# 1-Schematic_Antenna_Mini-Whip_SMD.net
KiCad netlist of a schematic drawn in EasyEDA
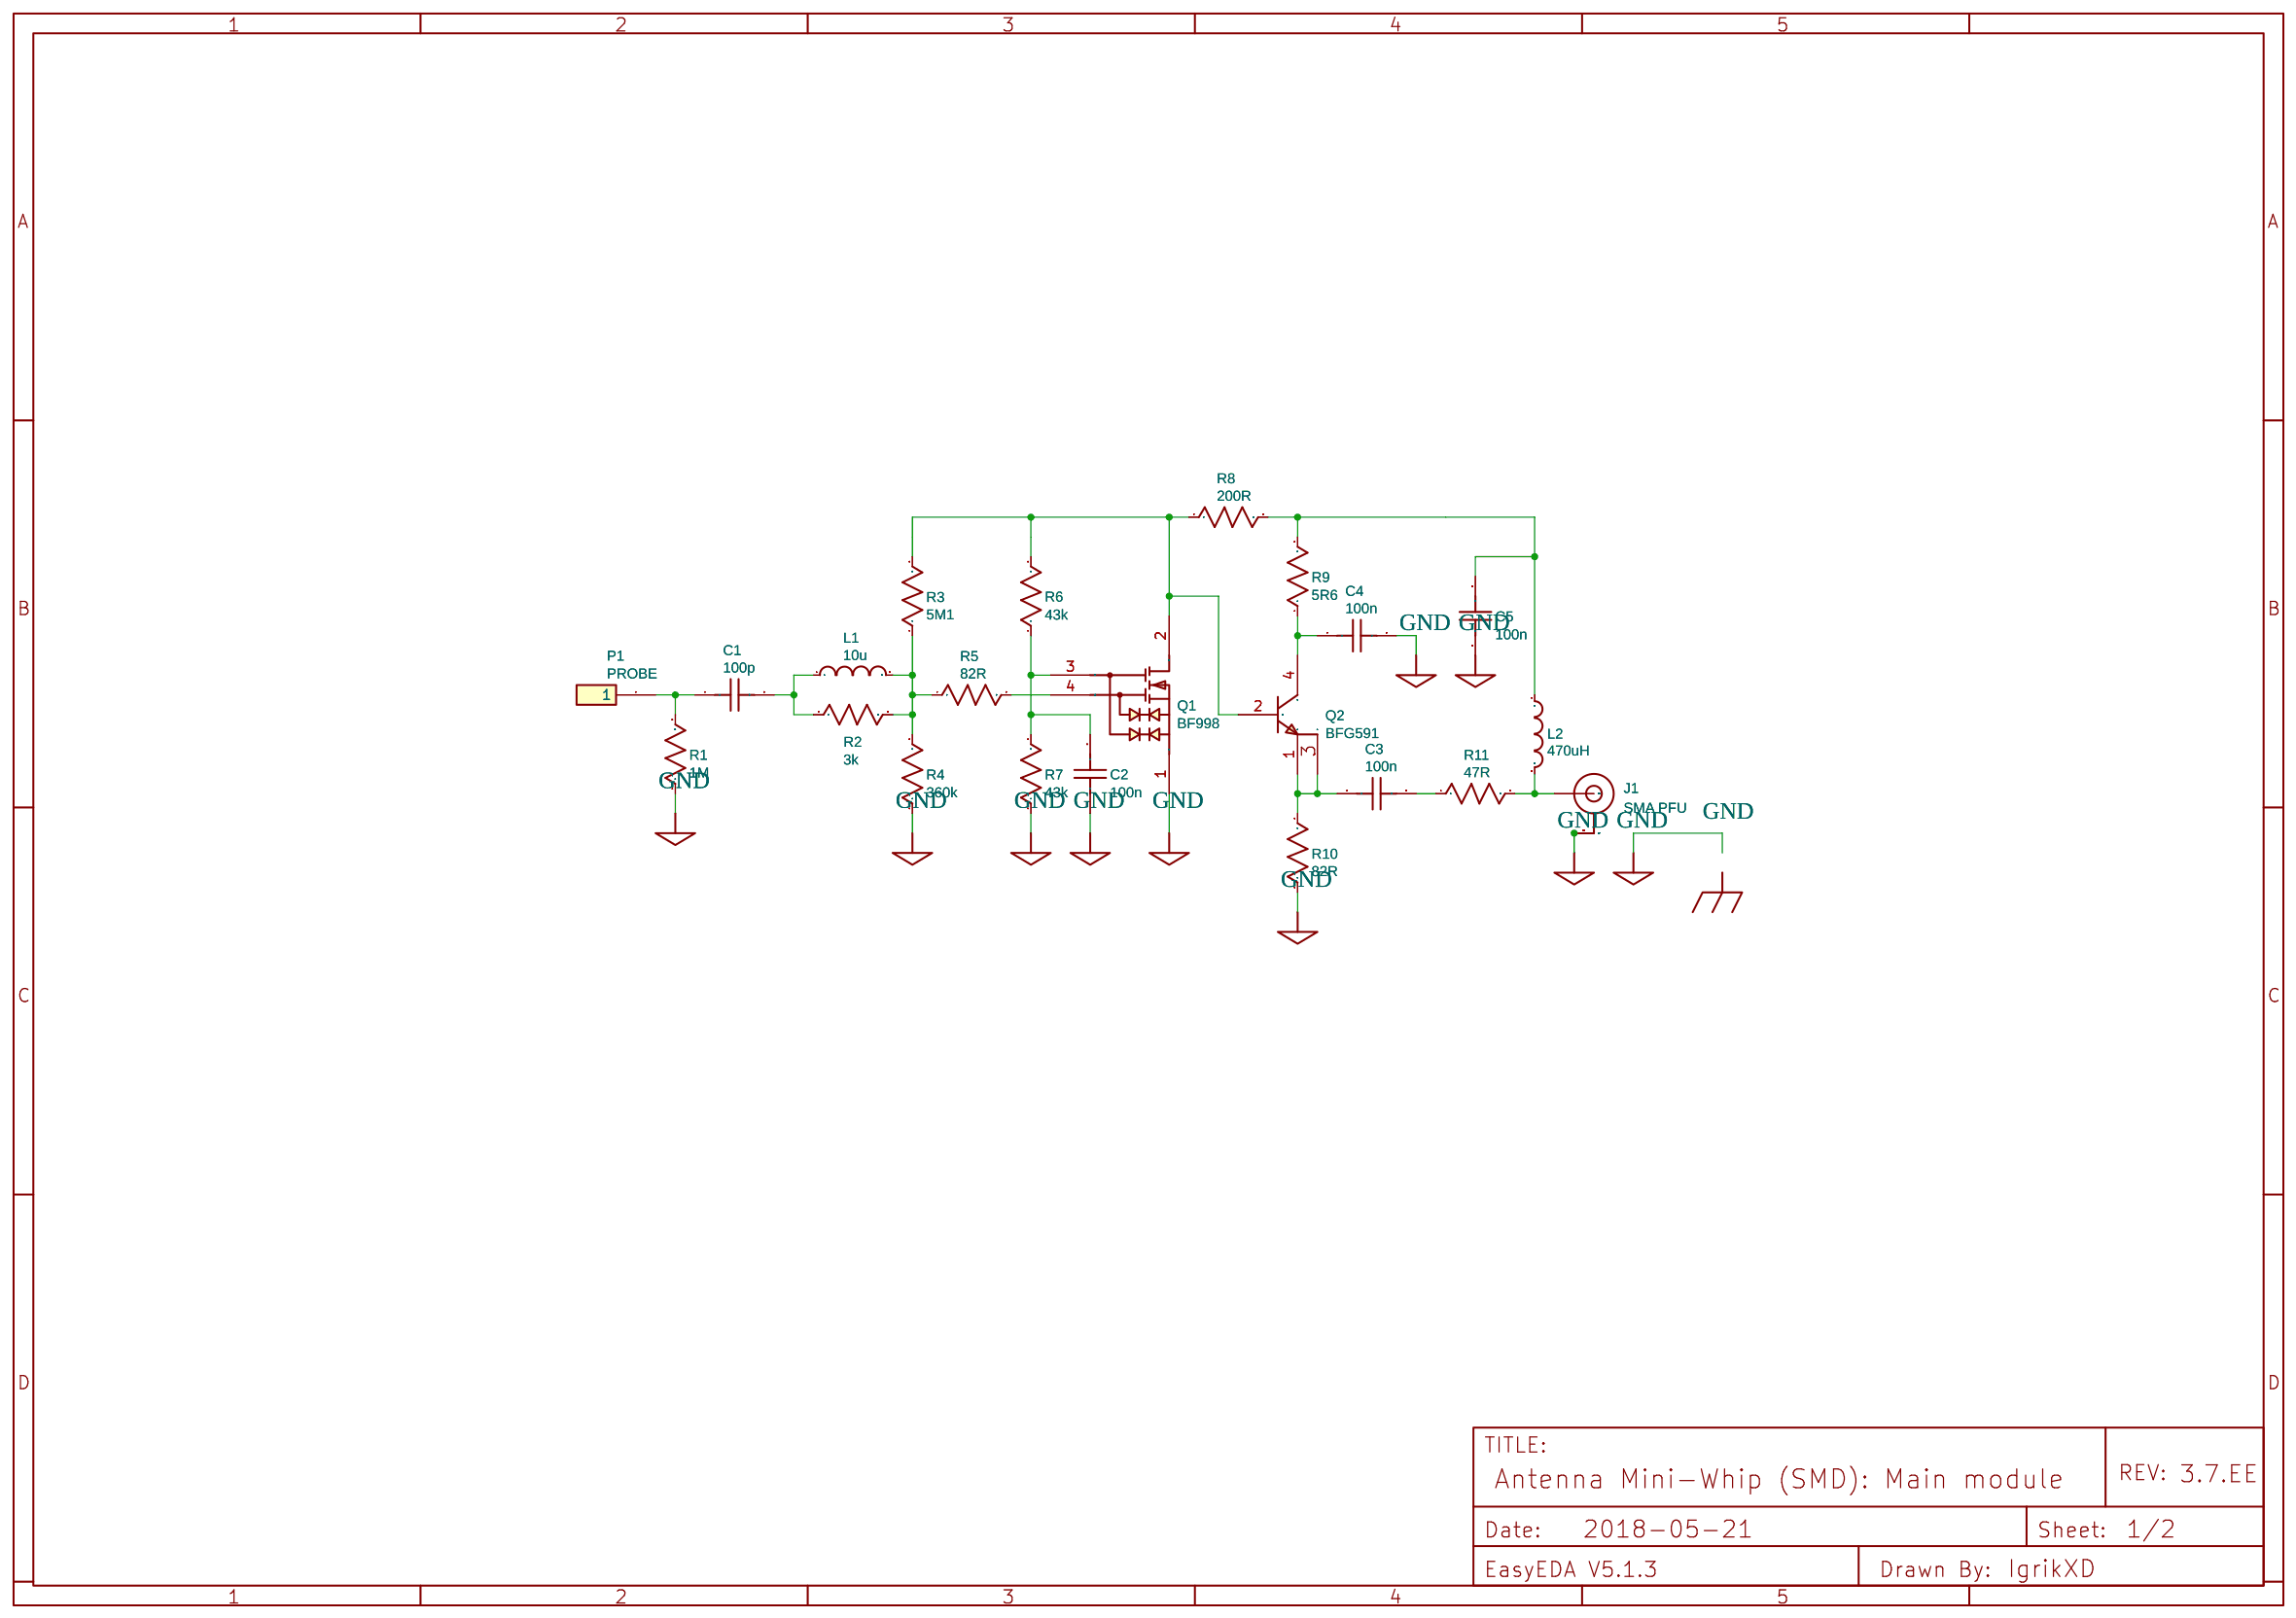
[diagram p0: Antenna Mini-Whip (SMD): Main module]
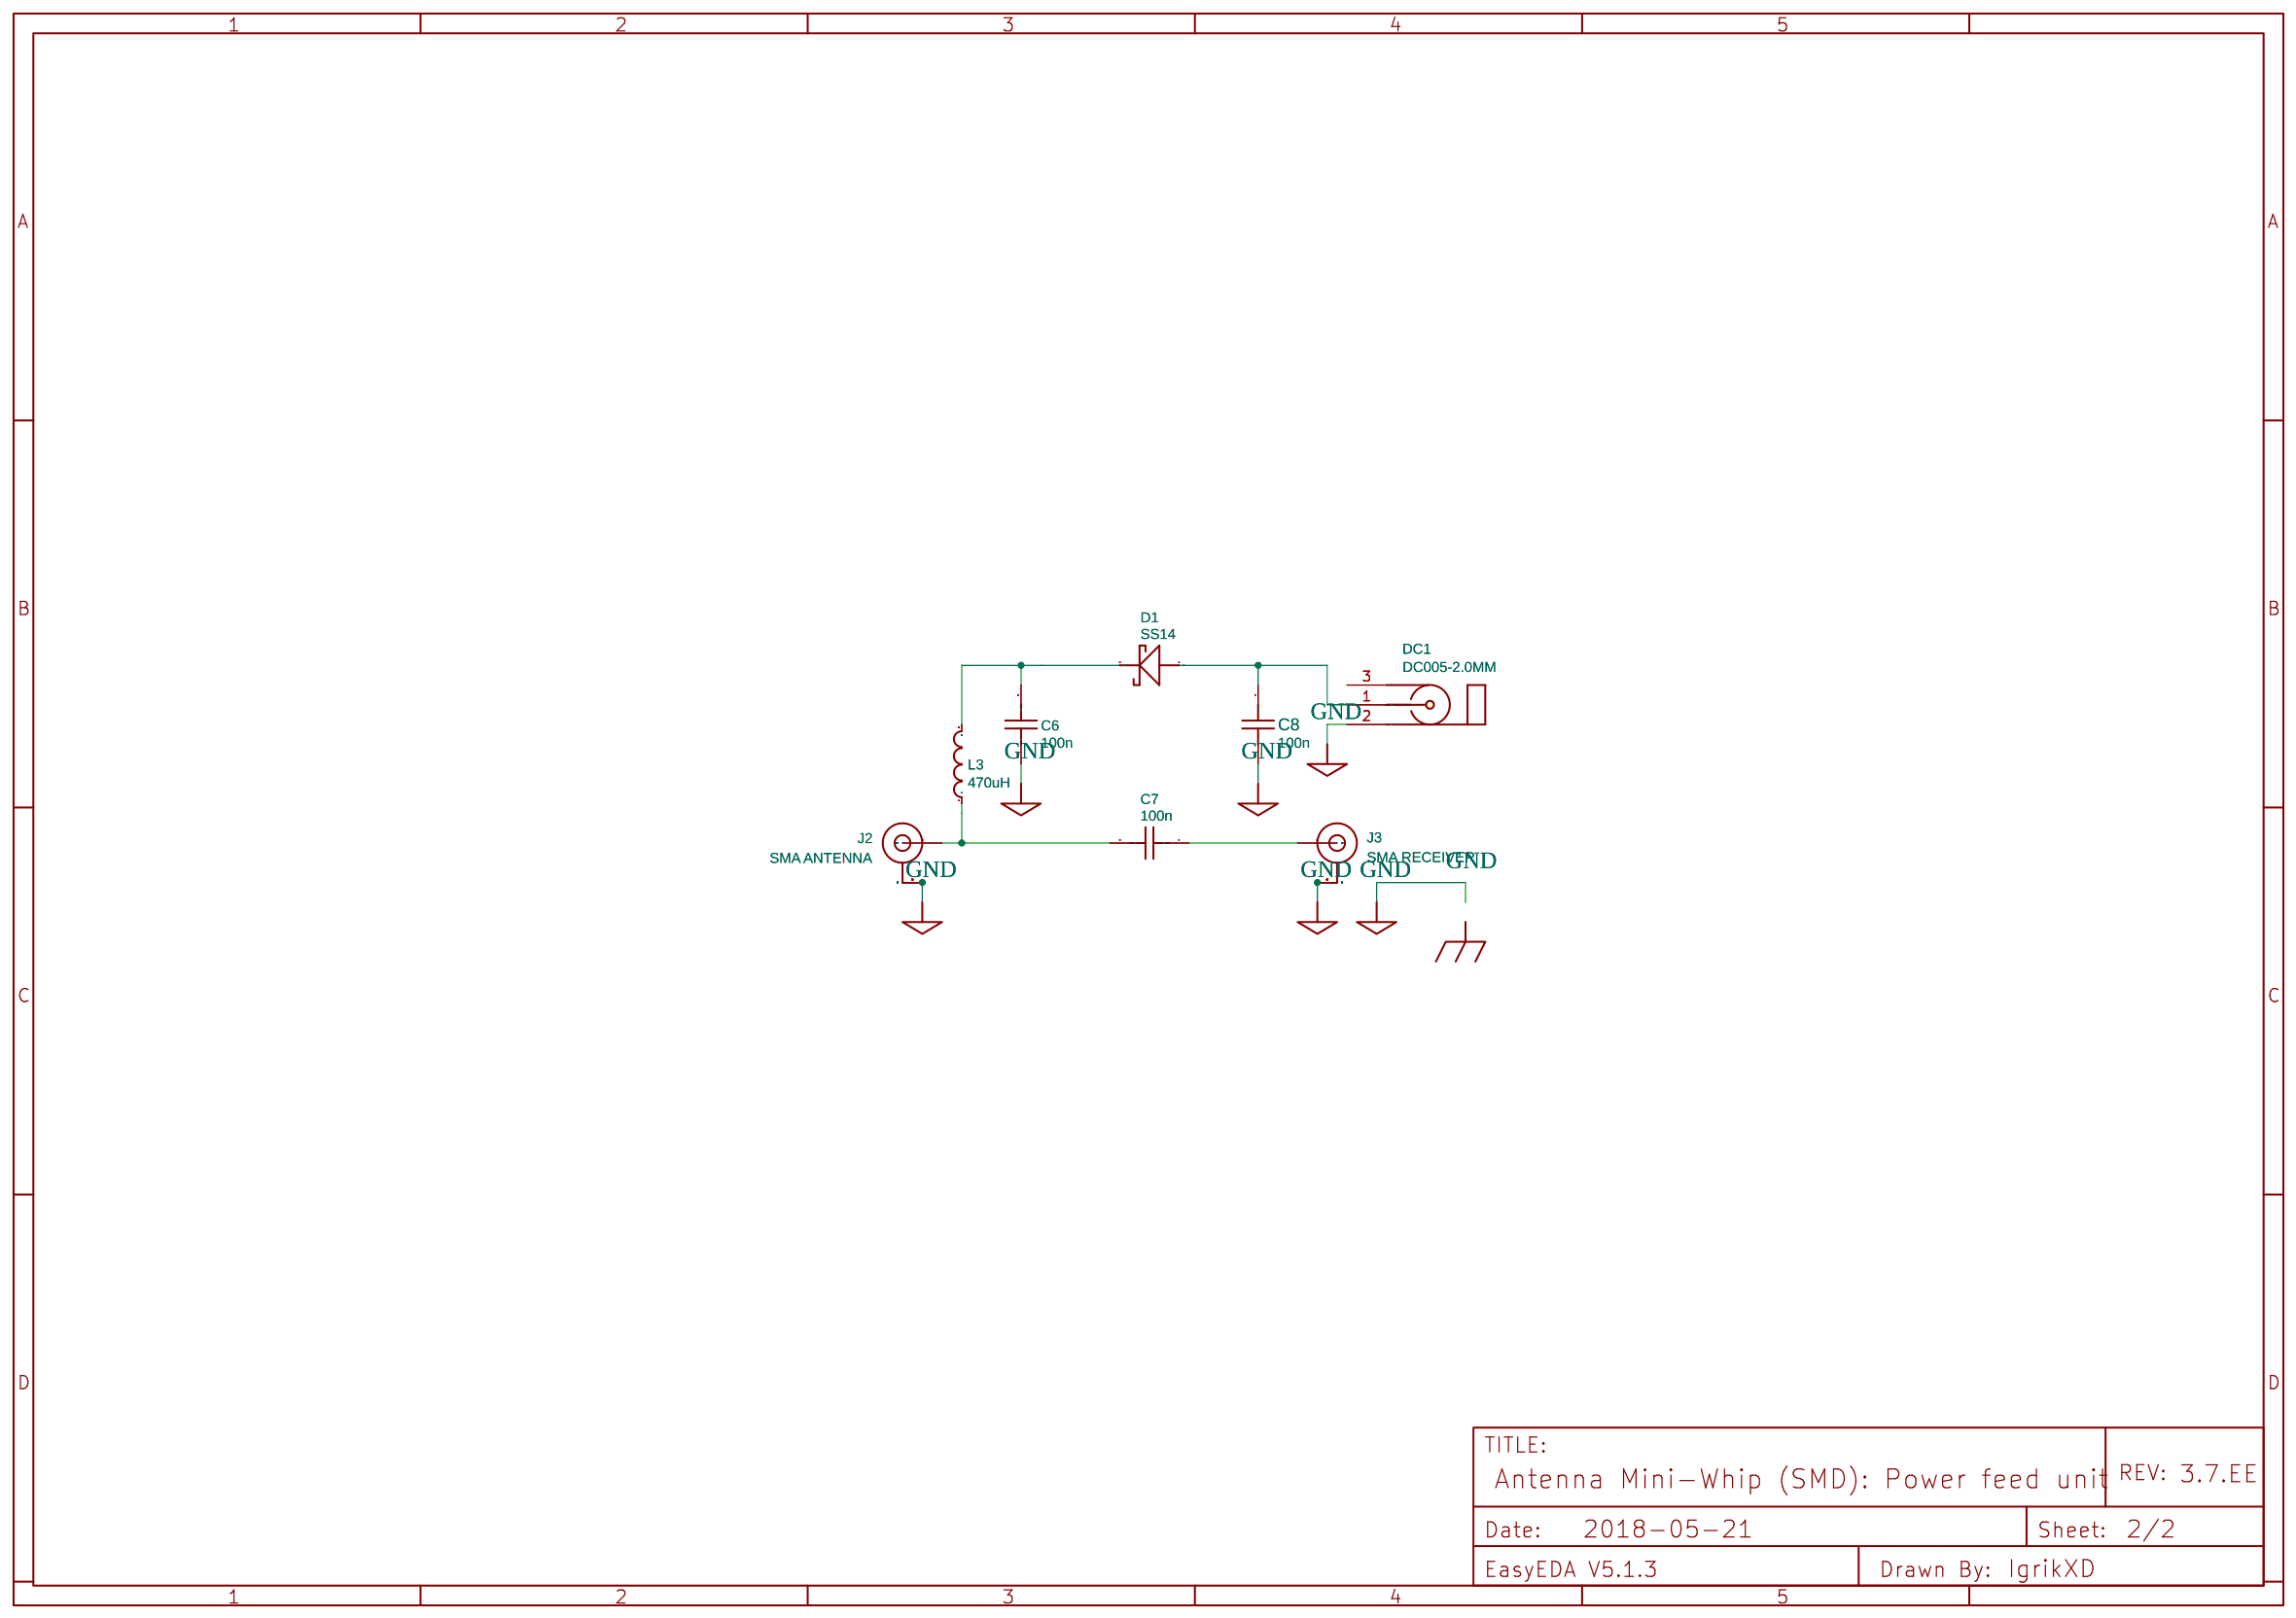
[diagram p1: Antenna Mini-Whip (SMD): Power feed unit]

(export (version "E")
  (design (tool "Eeschema 10.0.6"))
  (components
    (comp (ref "C1")
      (value "100p")
      (fields (field (name "BOM_Manufacturer Part") "CC0805JRNPOBBN101"))
      (libsource (lib "") (part "Capacitor"))
    )
    (comp (ref "C2")
      (value "100n")
      (fields (field (name "BOM_Manufacturer Part") "08055C104JAT2A"))
      (libsource (lib "") (part "Capacitor_1"))
    )
    (comp (ref "C3")
      (value "100n")
      (fields (field (name "BOM_Manufacturer Part") "08055C104JAT2A"))
      (libsource (lib "") (part "Capacitor"))
    )
    (comp (ref "C4")
      (value "100n")
      (fields (field (name "BOM_Manufacturer Part") "08055C104JAT2A"))
      (libsource (lib "") (part "Capacitor"))
    )
    (comp (ref "C5")
      (value "100n")
      (fields (field (name "BOM_Manufacturer Part") "08055C104JAT2A"))
      (libsource (lib "") (part "Capacitor_1"))
    )
    (comp (ref "J1")
      (value "SMA PFU")
      (fields (field (name "BOM_Manufacturer Part") "ANKX01.0093"))
      (libsource (lib "") (part "Unknown_800_395"))
    )
    (comp (ref "L1")
      (value "10u")
      (fields (field (name "BOM_Manufacturer Part") "MLF2012E100JT000"))
      (libsource (lib "") (part "Inductor"))
    )
    (comp (ref "L2")
      (value "470uH")
      (fields (field (name "BOM_Manufacturer Part") "SM7850-471MT"))
      (libsource (lib "") (part "Unknown_770_365"))
    )
    (comp (ref "P1")
      (value "PROBE")
      (fields (field (name "BOM_Manufacturer Part") "Header-Male-2.54_1x1"))
      (libsource (lib "") (part "Unknown_310_345"))
    )
    (comp (ref "Q1")
      (value "BF998")
      (fields (field (name "BOM_Manufacturer Part") "BF998E6327HTSA1"))
      (libsource (lib "") (part "Unknown_565_355"))
    )
    (comp (ref "Q2")
      (value "BFG591")
      (fields (field (name "BOM_Manufacturer Part") "BFG591,115"))
      (libsource (lib "") (part "Unknown_640_355"))
    )
    (comp (ref "R1")
      (value "1M")
      (fields (field (name "BOM_Manufacturer Part") "RC0805FR-071ML"))
      (libsource (lib "") (part "Resistor_1"))
    )
    (comp (ref "R2")
      (value "3k")
      (fields (field (name "BOM_Manufacturer Part") "RC0805FR-073KL"))
      (libsource (lib "") (part "Resistor"))
    )
    (comp (ref "R3")
      (value "5M1")
      (fields (field (name "BOM_Manufacturer Part") "RC0805FR-075M1L"))
      (libsource (lib "") (part "Resistor_1"))
    )
    (comp (ref "R4")
      (value "360k")
      (fields (field (name "BOM_Manufacturer Part") "RC0805FR-07360KL"))
      (libsource (lib "") (part "Resistor_1"))
    )
    (comp (ref "R5")
      (value "82R")
      (fields (field (name "BOM_Manufacturer Part") "RTT0582R0FTP"))
      (libsource (lib "") (part "Resistor"))
    )
    (comp (ref "R6")
      (value "43k")
      (fields (field (name "BOM_Manufacturer Part") "RTT054302FTP"))
      (libsource (lib "") (part "Resistor_1"))
    )
    (comp (ref "R7")
      (value "43k")
      (fields (field (name "BOM_Manufacturer Part") "RTT054302FTP"))
      (libsource (lib "") (part "Resistor_1"))
    )
    (comp (ref "R8")
      (value "200R")
      (fields (field (name "BOM_Manufacturer Part") "RC1206FR-07200RL"))
      (libsource (lib "") (part "Resistor"))
    )
    (comp (ref "R9")
      (value "5R6")
      (fields (field (name "BOM_Manufacturer Part") "CR0805F85R60G"))
      (libsource (lib "") (part "Resistor_1"))
    )
    (comp (ref "R10")
      (value "82R")
      (fields (field (name "BOM_Manufacturer Part") "CR2512J82RE042W"))
      (libsource (lib "") (part "Resistor_1"))
    )
    (comp (ref "R11")
      (value "47R")
      (fields (field (name "BOM_Manufacturer Part") "RTT0547R0FTP"))
      (libsource (lib "") (part "Resistor"))
    )
    (comp (ref "C6")
      (value "100n")
      (fields (field (name "BOM_Manufacturer Part") "08055C104JAT2A"))
      (libsource (lib "") (part "Capacitor"))
    )
    (comp (ref "C7")
      (value "100n")
      (fields (field (name "BOM_Manufacturer Part") "08055C104JAT2A"))
      (libsource (lib "") (part "Capacitor_1"))
    )
    (comp (ref "C8")
      (value "100n")
      (fields (field (name "BOM_Manufacturer Part") "08055C104JAT2A"))
      (libsource (lib "") (part "Capacitor"))
    )
    (comp (ref "D1")
      (value "SS14")
      (fields (field (name "BOM_Manufacturer Part") "SS14D"))
      (libsource (lib "") (part "Unknown_575_330"))
    )
    (comp (ref "DC1")
      (value "DC005-2.0MM")
      (fields (field (name "BOM_Manufacturer Part") "DC-005 5.5-2.0MM"))
      (libsource (lib "") (part "Unknown_705_350"))
    )
    (comp (ref "J2")
      (value "SMA ANTENNA")
      (fields (field (name "BOM_Manufacturer Part") "ANKX01.0093"))
      (libsource (lib "") (part "Unknown_450_420"))
    )
    (comp (ref "J3")
      (value "SMA RECEIVER")
      (fields (field (name "BOM_Manufacturer Part") "ANKX01.0093"))
      (libsource (lib "") (part "Unknown_670_420"))
    )
    (comp (ref "L3")
      (value "470uH")
      (fields (field (name "BOM_Manufacturer Part") "SM7850-471MT"))
      (libsource (lib "") (part "Unknown_480_380"))
    )
  )
  (nets
    (net (code "1") (name "GND") (class "Default")
      (node (ref "C2") (pin "1") (pinfunction "1_1") (pintype "unspecified"))
      (node (ref "C4") (pin "2") (pinfunction "2_2") (pintype "unspecified"))
      (node (ref "C5") (pin "1") (pinfunction "1_1") (pintype "unspecified"))
      (node (ref "C6") (pin "1") (pinfunction "1_1") (pintype "unspecified"))
      (node (ref "C8") (pin "1") (pinfunction "1_1") (pintype "unspecified"))
      (node (ref "DC1") (pin "2") (pinfunction "2_2") (pintype "input"))
      (node (ref "J1") (pin "GND@0") (pinfunction "GND_GND@0") (pintype "unspecified"))
      (node (ref "J1") (pin "GND@1") (pinfunction "GND_GND@1") (pintype "unspecified"))
      (node (ref "J1") (pin "GND@2") (pinfunction "GND_GND@2") (pintype "unspecified"))
      (node (ref "J1") (pin "GND@3") (pinfunction "GND_GND@3") (pintype "unspecified"))
      (node (ref "J2") (pin "GND@0") (pinfunction "GND_GND@0") (pintype "unspecified"))
      (node (ref "J2") (pin "GND@1") (pinfunction "GND_GND@1") (pintype "unspecified"))
      (node (ref "J2") (pin "GND@2") (pinfunction "GND_GND@2") (pintype "unspecified"))
      (node (ref "J2") (pin "GND@3") (pinfunction "GND_GND@3") (pintype "unspecified"))
      (node (ref "J3") (pin "GND@0") (pinfunction "GND_GND@0") (pintype "unspecified"))
      (node (ref "J3") (pin "GND@1") (pinfunction "GND_GND@1") (pintype "unspecified"))
      (node (ref "J3") (pin "GND@2") (pinfunction "GND_GND@2") (pintype "unspecified"))
      (node (ref "J3") (pin "GND@3") (pinfunction "GND_GND@3") (pintype "unspecified"))
      (node (ref "Q1") (pin "1") (pinfunction "S_1") (pintype "unspecified"))
      (node (ref "R1") (pin "1") (pinfunction "1_1") (pintype "unspecified"))
      (node (ref "R10") (pin "1") (pinfunction "1_1") (pintype "unspecified"))
      (node (ref "R4") (pin "1") (pinfunction "1_1") (pintype "unspecified"))
      (node (ref "R7") (pin "1") (pinfunction "1_1") (pintype "unspecified"))
    )
    (net (code "2") (name "Net-(C1-Pad1)") (class "Default")
      (node (ref "C1") (pin "1") (pinfunction "1_1") (pintype "unspecified"))
      (node (ref "P1") (pin "1") (pinfunction "1_1") (pintype "input"))
      (node (ref "R1") (pin "2") (pinfunction "2_2") (pintype "unspecified"))
    )
    (net (code "3") (name "Net-(C1-Pad2)") (class "Default")
      (node (ref "C1") (pin "2") (pinfunction "2_2") (pintype "unspecified"))
      (node (ref "L1") (pin "1") (pinfunction "1_1") (pintype "unspecified"))
      (node (ref "R2") (pin "1") (pinfunction "1_1") (pintype "unspecified"))
    )
    (net (code "4") (name "Net-(C3-Pad1)") (class "Default")
      (node (ref "C3") (pin "1") (pinfunction "1_1") (pintype "unspecified"))
      (node (ref "Q2") (pin "1") (pinfunction "E_1") (pintype "unspecified"))
      (node (ref "Q2") (pin "3") (pinfunction "E_3") (pintype "unspecified"))
      (node (ref "R10") (pin "2") (pinfunction "2_2") (pintype "unspecified"))
    )
    (net (code "5") (name "Net-(C3-Pad2)") (class "Default")
      (node (ref "C3") (pin "2") (pinfunction "2_2") (pintype "unspecified"))
      (node (ref "R11") (pin "1") (pinfunction "1_1") (pintype "unspecified"))
    )
    (net (code "6") (name "Net-(C5-Pad2)") (class "Default")
      (node (ref "C5") (pin "2") (pinfunction "2_2") (pintype "unspecified"))
      (node (ref "L2") (pin "1") (pinfunction "1_1") (pintype "unspecified"))
      (node (ref "R8") (pin "2") (pinfunction "2_2") (pintype "unspecified"))
      (node (ref "R9") (pin "2") (pinfunction "2_2") (pintype "unspecified"))
    )
    (net (code "7") (name "Net-(D1-A)") (class "Default")
      (node (ref "C8") (pin "2") (pinfunction "2_2") (pintype "unspecified"))
      (node (ref "D1") (pin "1") (pinfunction "A_1") (pintype "unspecified"))
      (node (ref "DC1") (pin "1") (pinfunction "VCC_1") (pintype "input"))
    )
    (net (code "8") (name "Net-(D1-C)") (class "Default")
      (node (ref "C6") (pin "2") (pinfunction "2_2") (pintype "unspecified"))
      (node (ref "D1") (pin "2") (pinfunction "C_2") (pintype "unspecified"))
      (node (ref "L3") (pin "2") (pinfunction "2_2") (pintype "unspecified"))
    )
    (net (code "9") (name "Net-(J1-SIGNAL)") (class "Default")
      (node (ref "J1") (pin "SIG") (pinfunction "SIGNAL_SIG") (pintype "unspecified"))
      (node (ref "L2") (pin "2") (pinfunction "2_2") (pintype "unspecified"))
      (node (ref "R11") (pin "2") (pinfunction "2_2") (pintype "unspecified"))
    )
    (net (code "10") (name "Net-(J2-SIGNAL)") (class "Default")
      (node (ref "C7") (pin "2") (pinfunction "2_2") (pintype "unspecified"))
      (node (ref "J2") (pin "SIG") (pinfunction "SIGNAL_SIG") (pintype "unspecified"))
      (node (ref "L3") (pin "1") (pinfunction "1_1") (pintype "unspecified"))
    )
    (net (code "11") (name "Net-(J3-SIGNAL)") (class "Default")
      (node (ref "C7") (pin "1") (pinfunction "1_1") (pintype "unspecified"))
      (node (ref "J3") (pin "SIG") (pinfunction "SIGNAL_SIG") (pintype "unspecified"))
    )
    (net (code "12") (name "Net-(L1-Pad2)") (class "Default")
      (node (ref "L1") (pin "2") (pinfunction "2_2") (pintype "unspecified"))
      (node (ref "R2") (pin "2") (pinfunction "2_2") (pintype "unspecified"))
      (node (ref "R3") (pin "1") (pinfunction "1_1") (pintype "unspecified"))
      (node (ref "R4") (pin "2") (pinfunction "2_2") (pintype "unspecified"))
      (node (ref "R5") (pin "1") (pinfunction "1_1") (pintype "unspecified"))
    )
    (net (code "13") (name "Net-(Q1-D)") (class "Default")
      (node (ref "Q1") (pin "2") (pinfunction "D_2") (pintype "unspecified"))
      (node (ref "Q2") (pin "2") (pinfunction "B_2") (pintype "unspecified"))
      (node (ref "R3") (pin "2") (pinfunction "2_2") (pintype "unspecified"))
      (node (ref "R6") (pin "2") (pinfunction "2_2") (pintype "unspecified"))
      (node (ref "R8") (pin "1") (pinfunction "1_1") (pintype "unspecified"))
    )
    (net (code "14") (name "Net-(Q1-G1)") (class "Default")
      (node (ref "Q1") (pin "4") (pinfunction "G1_4") (pintype "unspecified"))
      (node (ref "R5") (pin "2") (pinfunction "2_2") (pintype "unspecified"))
    )
    (net (code "15") (name "Net-(Q1-G2)") (class "Default")
      (node (ref "C2") (pin "2") (pinfunction "2_2") (pintype "unspecified"))
      (node (ref "Q1") (pin "3") (pinfunction "G2_3") (pintype "unspecified"))
      (node (ref "R6") (pin "1") (pinfunction "1_1") (pintype "unspecified"))
      (node (ref "R7") (pin "2") (pinfunction "2_2") (pintype "unspecified"))
    )
    (net (code "16") (name "Net-(Q2-C)") (class "Default")
      (node (ref "C4") (pin "1") (pinfunction "1_1") (pintype "unspecified"))
      (node (ref "Q2") (pin "4") (pinfunction "C_4") (pintype "unspecified"))
      (node (ref "R9") (pin "1") (pinfunction "1_1") (pintype "unspecified"))
    )
    (net (code "17") (name "unconnected-(DC1-Pad3)") (class "Default")
      (node (ref "DC1") (pin "3") (pinfunction "3_3") (pintype "input"))
    )
  )
)
